# POWER.net
KiCad netlist of a schematic drawn in Altium Designer
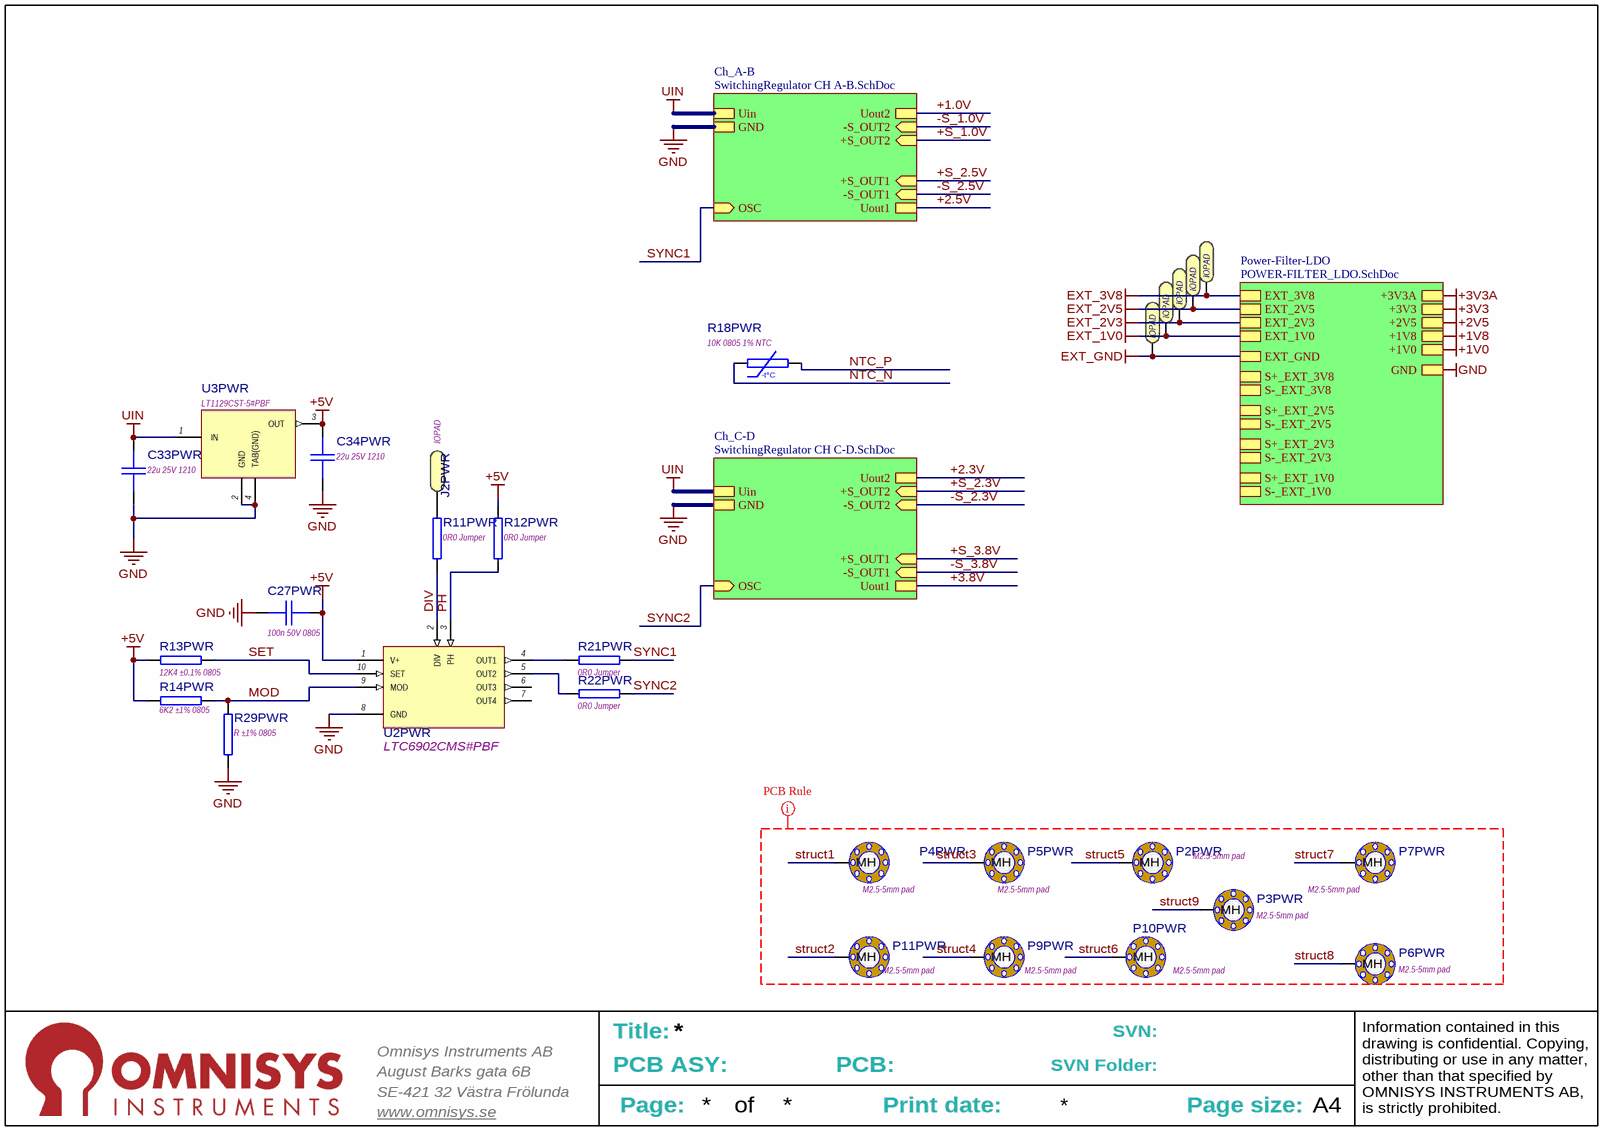
[diagram p0: POWER.SchDoc]

(export (version "E")
  (design (tool "Eeschema 10.0.6"))
  (components
    (comp (ref "C27PWR")
      (value "100n 50V 0805")
      (footprint "CAPC2012X135N")
      (description "100n 50V X7R ±10% 0805 (2012 metric)")
      (fields (field (name "TOLERANCE") "10%") (field (name "PARTNUMBER") "GRM21BR71H104KA01"))
      (libsource (lib "Omnisys Vault") (part "CAP-2PIN"))
    )
    (comp (ref "C33PWR")
      (value "22u 25V 1210")
      (footprint "CAPC3225X270N")
      (description "22u 25V X7R ±10% 1210 (3225 metric)")
      (fields (field (name "TOLERANCE") "10%") (field (name "PARTNUMBER") "GRM32ER71E226ME15"))
      (libsource (lib "Omnisys Vault") (part "CAP-2PIN"))
    )
    (comp (ref "C34PWR")
      (value "22u 25V 1210")
      (footprint "CAPC3225X270N")
      (description "22u 25V X7R ±10% 1210 (3225 metric)")
      (fields (field (name "TOLERANCE") "10%") (field (name "PARTNUMBER") "GRM32ER71E226ME15"))
      (libsource (lib "Omnisys Vault") (part "CAP-2PIN"))
    )
    (comp (ref "J2PWR")
      (value "IOPAD")
      (footprint "SMT_IO_PAD_2x1MM")
      (description "IO pad used for test points and flying leads.")
      (libsource (lib "Omnisys Vault") (part "SMT_IOPAD"))
    )
    (comp (ref "J16")
      (value "IOPAD")
      (footprint "SMT_IO_PAD_2x1MM")
      (description "IO pad used for test points and flying leads.")
      (libsource (lib "Omnisys Vault") (part "SMT_IOPAD"))
    )
    (comp (ref "J17")
      (value "IOPAD")
      (footprint "SMT_IO_PAD_2x1MM")
      (description "IO pad used for test points and flying leads.")
      (libsource (lib "Omnisys Vault") (part "SMT_IOPAD"))
    )
    (comp (ref "J18")
      (value "IOPAD")
      (footprint "SMT_IO_PAD_2x1MM")
      (description "IO pad used for test points and flying leads.")
      (libsource (lib "Omnisys Vault") (part "SMT_IOPAD"))
    )
    (comp (ref "J19")
      (value "IOPAD")
      (footprint "SMT_IO_PAD_2x1MM")
      (description "IO pad used for test points and flying leads.")
      (libsource (lib "Omnisys Vault") (part "SMT_IOPAD"))
    )
    (comp (ref "J20")
      (value "IOPAD")
      (footprint "SMT_IO_PAD_2x1MM")
      (description "IO pad used for test points and flying leads.")
      (libsource (lib "Omnisys Vault") (part "SMT_IOPAD"))
    )
    (comp (ref "P2PWR")
      (value "M2.5-5mm pad")
      (footprint "MH5-2_7MM")
      (description "Mounting hole, M2.5-5mm pad")
      (libsource (lib "Omnisys Vault") (part "MH"))
    )
    (comp (ref "P3PWR")
      (value "M2.5-5mm pad")
      (footprint "MH5-2_7MM")
      (description "Mounting hole, M2.5-5mm pad")
      (libsource (lib "Omnisys Vault") (part "MH"))
    )
    (comp (ref "P4PWR")
      (value "M2.5-5mm pad")
      (footprint "MH5-2_7MM")
      (description "Mounting hole, M2.5-5mm pad")
      (libsource (lib "Omnisys Vault") (part "MH"))
    )
    (comp (ref "P5PWR")
      (value "M2.5-5mm pad")
      (footprint "MH5-2_7MM")
      (description "Mounting hole, M2.5-5mm pad")
      (libsource (lib "Omnisys Vault") (part "MH"))
    )
    (comp (ref "P6PWR")
      (value "M2.5-5mm pad")
      (footprint "MH5-2_7MM")
      (description "Mounting hole, M2.5-5mm pad")
      (libsource (lib "Omnisys Vault") (part "MH"))
    )
    (comp (ref "P7PWR")
      (value "M2.5-5mm pad")
      (footprint "MH5-2_7MM")
      (description "Mounting hole, M2.5-5mm pad")
      (libsource (lib "Omnisys Vault") (part "MH"))
    )
    (comp (ref "P9PWR")
      (value "M2.5-5mm pad")
      (footprint "MH5-2_7MM")
      (description "Mounting hole, M2.5-5mm pad")
      (libsource (lib "Omnisys Vault") (part "MH"))
    )
    (comp (ref "P10PWR")
      (value "M2.5-5mm pad")
      (footprint "MH5-2_7MM")
      (description "Mounting hole, M2.5-5mm pad")
      (libsource (lib "Omnisys Vault") (part "MH"))
    )
    (comp (ref "P11PWR")
      (value "M2.5-5mm pad")
      (footprint "MH5-2_7MM")
      (description "Mounting hole, M2.5-5mm pad")
      (libsource (lib "Omnisys Vault") (part "MH"))
    )
    (comp (ref "R11PWR")
      (value "0R0 Jumper")
      (footprint "RESC2012N")
      (description "0R0 Jumper 150V 0805 (2012 metric) Max 2.5A")
      (fields (field (name "TOLERANCE") "0%") (field (name "POWER") "0W"))
      (libsource (lib "Omnisys Vault") (part "RES-2PIN"))
    )
    (comp (ref "R12PWR")
      (value "0R0 Jumper")
      (footprint "RESC2012N")
      (description "0R0 Jumper 150V 0805 (2012 metric) Max 2.5A")
      (fields (field (name "TOLERANCE") "0%") (field (name "POWER") "0W"))
      (libsource (lib "Omnisys Vault") (part "RES-2PIN"))
    )
    (comp (ref "R13PWR")
      (value "12K4 ±0.1% 0805")
      (footprint "RESC2012N")
      (description "12K4 ±0.1% ±10 ppm/˚C 0.1W 100V 0805 (2012 metric) Thinfilm")
      (fields (field (name "POWER") "0.1W") (field (name "TOLERANCE") "±0.1"))
      (libsource (lib "Omnisys Vault") (part "RES-2PIN"))
    )
    (comp (ref "R14PWR")
      (value "6K2 ±1% 0805")
      (footprint "RESC2012N")
      (description "6K2 ±1% ±100 ppm/˚C 0.125W 150V 0805 (2012 metric)")
      (fields (field (name "TOLERANCE") "1%") (field (name "POWER") "125mW"))
      (libsource (lib "Omnisys Vault") (part "RES-2PIN"))
    )
    (comp (ref "R18PWR")
      (value "10K 0805 1% NTC")
      (footprint "RESC2012N")
      (description "10K NTC resistor 1%  0805 (2012 metric)")
      (fields (field (name "PARTNUMBER") "NTCS0805E3103FLT"))
      (libsource (lib "Omnisys Vault") (part "RES-2PIN-NTC"))
    )
    (comp (ref "R21PWR")
      (value "0R0 Jumper")
      (footprint "RESC2012N")
      (description "0R0 Jumper 150V 0805 (2012 metric) Max 2.5A")
      (fields (field (name "TOLERANCE") "0%") (field (name "POWER") "0W"))
      (libsource (lib "Omnisys Vault") (part "RES-2PIN"))
    )
    (comp (ref "R22PWR")
      (value "0R0 Jumper")
      (footprint "RESC2012N")
      (description "0R0 Jumper 150V 0805 (2012 metric) Max 2.5A")
      (fields (field (name "TOLERANCE") "0%") (field (name "POWER") "0W"))
      (libsource (lib "Omnisys Vault") (part "RES-2PIN"))
    )
    (comp (ref "R29PWR")
      (value "R ±1% 0805")
      (footprint "RESC2012N")
      (description "R ±1% 0.125W 150V 0805 (2012 metric)")
      (fields (field (name "POWER") "125mW") (field (name "TOLERANCE") "0%"))
      (libsource (lib "Omnisys Vault") (part "RES-2PIN"))
    )
    (comp (ref "U2PWR")
      (value "LTC6902CMS#PBF")
      (footprint "TSSOP50P490X110-10N")
      (description "LINEAR TECHNOLOGY         LTC6902CMS#PBF            OSCILLATOR, 5KHZ - 20MHZ, 10MSOP")
      (libsource (lib "Omnisys Vault") (part "LTC6902CMS#PBF"))
    )
    (comp (ref "U3PWR")
      (value "LT1129CST-5#PBF")
      (footprint "SOT230P700X180-4N")
      (description "700mA, Micropower Low Dropout Regulators, LT1129CST-5#PBF")
      (libsource (lib "Omnisys Vault") (part "LDO-LT-SOT-223"))
    )
  )
  (nets
    (net (code "6") (name "+5V") (class "Default")
      (node (ref "C27PWR") (pin "1") (pinfunction "1_1") (pintype "passive"))
      (node (ref "C34PWR") (pin "1") (pinfunction "1_1") (pintype "passive"))
      (node (ref "R12PWR") (pin "1") (pinfunction "1_1") (pintype "passive"))
      (node (ref "R13PWR") (pin "2") (pinfunction "2_2") (pintype "passive"))
      (node (ref "R14PWR") (pin "2") (pinfunction "2_2") (pintype "passive"))
      (node (ref "U2PWR") (pin "1") (pinfunction "V+_1") (pintype "power_in"))
      (node (ref "U3PWR") (pin "3") (pinfunction "OUT_3") (pintype "output"))
    )
    (net (code "19") (name "/DIV") (class "Default")
      (node (ref "R11PWR") (pin "2") (pinfunction "2_2") (pintype "passive"))
      (node (ref "U2PWR") (pin "2") (pinfunction "DIV_2") (pintype "input"))
    )
    (net (code "20") (name "/MOD") (class "Default")
      (node (ref "R14PWR") (pin "1") (pinfunction "1_1") (pintype "passive"))
      (node (ref "R29PWR") (pin "2") (pinfunction "2_2") (pintype "passive"))
      (node (ref "U2PWR") (pin "9") (pinfunction "MOD_9") (pintype "input"))
    )
    (net (code "21") (name "/NTC_N") (class "Default")
      (node (ref "R18PWR") (pin "1") (pinfunction "1_1") (pintype "passive"))
    )
    (net (code "22") (name "/NTC_P") (class "Default")
      (node (ref "R18PWR") (pin "2") (pinfunction "2_2") (pintype "passive"))
    )
    (net (code "23") (name "/PH") (class "Default")
      (node (ref "R12PWR") (pin "2") (pinfunction "2_2") (pintype "passive"))
      (node (ref "U2PWR") (pin "3") (pinfunction "PH_3") (pintype "input"))
    )
    (net (code "32") (name "/SET") (class "Default")
      (node (ref "R13PWR") (pin "1") (pinfunction "1_1") (pintype "passive"))
      (node (ref "U2PWR") (pin "10") (pinfunction "SET_10") (pintype "input"))
    )
    (net (code "33") (name "/SYNC1") (class "Default")
      (node (ref "R21PWR") (pin "2") (pinfunction "2_2") (pintype "passive"))
    )
    (net (code "34") (name "/SYNC2") (class "Default")
      (node (ref "R22PWR") (pin "2") (pinfunction "2_2") (pintype "passive"))
    )
    (net (code "35") (name "/struct1") (class "Default")
      (node (ref "P4PWR") (pin "MH") (pinfunction "MH_MH") (pintype "passive"))
    )
    (net (code "36") (name "/struct2") (class "Default")
      (node (ref "P11PWR") (pin "MH") (pinfunction "MH_MH") (pintype "passive"))
    )
    (net (code "37") (name "/struct3") (class "Default")
      (node (ref "P5PWR") (pin "MH") (pinfunction "MH_MH") (pintype "passive"))
    )
    (net (code "38") (name "/struct4") (class "Default")
      (node (ref "P9PWR") (pin "MH") (pinfunction "MH_MH") (pintype "passive"))
    )
    (net (code "39") (name "/struct5") (class "Default")
      (node (ref "P2PWR") (pin "MH") (pinfunction "MH_MH") (pintype "passive"))
    )
    (net (code "40") (name "/struct6") (class "Default")
      (node (ref "P10PWR") (pin "MH") (pinfunction "MH_MH") (pintype "passive"))
    )
    (net (code "41") (name "/struct7") (class "Default")
      (node (ref "P7PWR") (pin "MH") (pinfunction "MH_MH") (pintype "passive"))
    )
    (net (code "42") (name "/struct8") (class "Default")
      (node (ref "P6PWR") (pin "MH") (pinfunction "MH_MH") (pintype "passive"))
    )
    (net (code "43") (name "/struct9") (class "Default")
      (node (ref "P3PWR") (pin "MH") (pinfunction "MH_MH") (pintype "passive"))
    )
    (net (code "44") (name "EXT_1V0") (class "Default")
      (node (ref "J19") (pin "1") (pinfunction "1_1") (pintype "passive"))
    )
    (net (code "45") (name "EXT_2V3") (class "Default")
      (node (ref "J18") (pin "1") (pinfunction "1_1") (pintype "passive"))
    )
    (net (code "46") (name "EXT_2V5") (class "Default")
      (node (ref "J17") (pin "1") (pinfunction "1_1") (pintype "passive"))
    )
    (net (code "47") (name "EXT_3V8") (class "Default")
      (node (ref "J16") (pin "1") (pinfunction "1_1") (pintype "passive"))
    )
    (net (code "48") (name "EXT_GND") (class "Default")
      (node (ref "J20") (pin "1") (pinfunction "1_1") (pintype "passive"))
    )
    (net (code "49") (name "GND") (class "Default")
      (node (ref "C27PWR") (pin "2") (pinfunction "2_2") (pintype "passive"))
      (node (ref "C33PWR") (pin "2") (pinfunction "2_2") (pintype "passive"))
      (node (ref "C34PWR") (pin "2") (pinfunction "2_2") (pintype "passive"))
      (node (ref "R29PWR") (pin "1") (pinfunction "1_1") (pintype "passive"))
      (node (ref "U2PWR") (pin "8") (pinfunction "GND_8") (pintype "power_in"))
      (node (ref "U3PWR") (pin "2") (pinfunction "GND_2") (pintype "passive"))
      (node (ref "U3PWR") (pin "4") (pinfunction "TAB(GND)_4") (pintype "passive"))
    )
    (net (code "50") (name "Net-(J2PWR-Pad1)") (class "Default")
      (node (ref "J2PWR") (pin "1") (pinfunction "1_1") (pintype "passive"))
      (node (ref "R11PWR") (pin "1") (pinfunction "1_1") (pintype "passive"))
    )
    (net (code "51") (name "Net-(U2PWR-OUT1)") (class "Default")
      (node (ref "R21PWR") (pin "1") (pinfunction "1_1") (pintype "passive"))
      (node (ref "U2PWR") (pin "4") (pinfunction "OUT1_4") (pintype "output"))
    )
    (net (code "52") (name "Net-(U2PWR-OUT2)") (class "Default")
      (node (ref "R22PWR") (pin "1") (pinfunction "1_1") (pintype "passive"))
      (node (ref "U2PWR") (pin "5") (pinfunction "OUT2_5") (pintype "output"))
    )
    (net (code "53") (name "UIN") (class "Default")
      (node (ref "C33PWR") (pin "1") (pinfunction "1_1") (pintype "passive"))
      (node (ref "U3PWR") (pin "1") (pinfunction "IN_1") (pintype "passive"))
    )
    (net (code "54") (name "unconnected-(U2PWR-OUT3-Pad6)") (class "Default")
      (node (ref "U2PWR") (pin "6") (pinfunction "OUT3_6") (pintype "output"))
    )
    (net (code "55") (name "unconnected-(U2PWR-OUT4-Pad7)") (class "Default")
      (node (ref "U2PWR") (pin "7") (pinfunction "OUT4_7") (pintype "output"))
    )
  )
)
